# FT232_V2.net
KiCad netlist of a schematic drawn in EAGLE
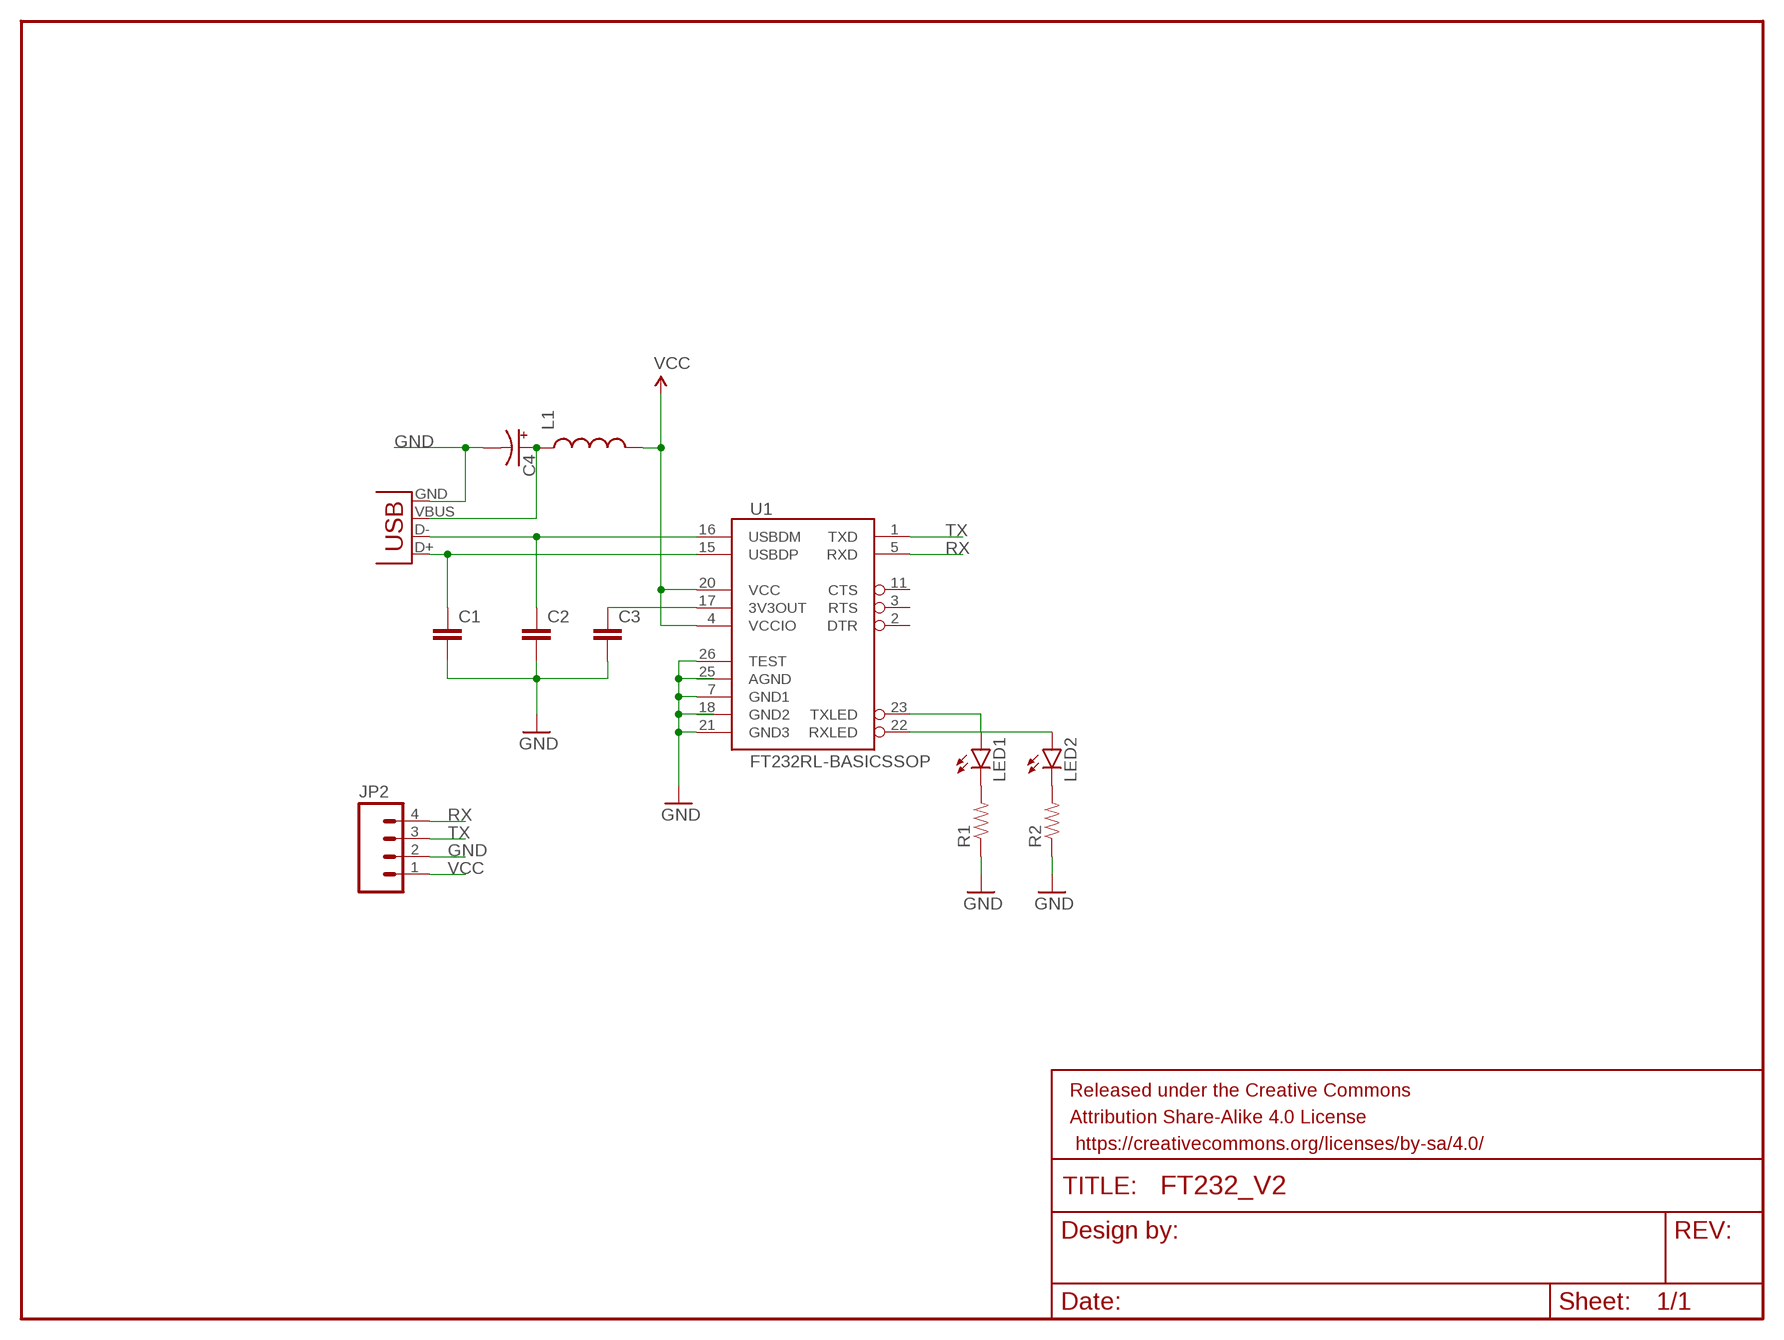
[diagram p0: schematic, sheet 1]

(export (version "E")
  (design (tool "Eeschema 10.0.6"))
  (components
    (comp (ref "C1")
      (value "CAP0603-CAP")
      (footprint "eagle-import:0603-CAP")
      (libsource (lib "eagle-import") (part "CAP0603-CAP"))
    )
    (comp (ref "C2")
      (value "CAP0603-CAP")
      (footprint "eagle-import:0603-CAP")
      (libsource (lib "eagle-import") (part "CAP0603-CAP"))
    )
    (comp (ref "C3")
      (value "CAP0603-CAP")
      (footprint "eagle-import:0603-CAP")
      (libsource (lib "eagle-import") (part "CAP0603-CAP"))
    )
    (comp (ref "C4")
      (value "CAP_POL1206")
      (footprint "eagle-import:EIA3216")
      (libsource (lib "eagle-import") (part "CAP_POL1206"))
    )
    (comp (ref "FRAME1")
      (value "FRAME-LETTER")
      (footprint "eagle-import:CREATIVE_COMMONS")
      (libsource (lib "eagle-import") (part "FRAME-LETTER"))
    )
    (comp (ref "JP1")
      (value "USB-B")
      (footprint "eagle-import:USB-B-PTH")
      (libsource (lib "eagle-import") (part "USBPTH"))
    )
    (comp (ref "JP2")
      (value "M04PTH")
      (footprint "eagle-import:1X04")
      (libsource (lib "eagle-import") (part "M04PTH"))
    )
    (comp (ref "L1")
      (value "INDUCTOR0603")
      (footprint "eagle-import:0603")
      (libsource (lib "eagle-import") (part "INDUCTOR0603"))
    )
    (comp (ref "LED1")
      (value "LED0603")
      (footprint "eagle-import:LED-0603")
      (libsource (lib "eagle-import") (part "LED0603"))
    )
    (comp (ref "LED2")
      (value "LED0603")
      (footprint "eagle-import:LED-0603")
      (libsource (lib "eagle-import") (part "LED0603"))
    )
    (comp (ref "R1")
      (value "RESISTOR0603")
      (footprint "eagle-import:0603-RES")
      (libsource (lib "eagle-import") (part "RESISTOR0603"))
    )
    (comp (ref "R2")
      (value "RESISTOR0603")
      (footprint "eagle-import:0603-RES")
      (libsource (lib "eagle-import") (part "RESISTOR0603"))
    )
    (comp (ref "U1")
      (value "FT232RL-BASICSSOP")
      (footprint "eagle-import:SSOP28DB")
      (libsource (lib "eagle-import") (part "FT232RL-BASICSSOP"))
    )
  )
  (nets
    (net (code "1") (name "/AGND") (class "Default")
      (node (ref "U1") (pin "25") (pinfunction "AGND_25") (pintype "power_in"))
    )
    (net (code "2") (name "/GND2") (class "Default")
      (node (ref "U1") (pin "18") (pinfunction "GND2_18") (pintype "power_in"))
    )
    (net (code "3") (name "/RX") (class "Default")
      (node (ref "JP2") (pin "4") (pinfunction "4_4") (pintype "passive"))
      (node (ref "U1") (pin "5") (pinfunction "RXD_5") (pintype "input"))
    )
    (net (code "4") (name "/TX") (class "Default")
      (node (ref "JP2") (pin "3") (pinfunction "3_3") (pintype "passive"))
      (node (ref "U1") (pin "1") (pinfunction "TXD_1") (pintype "output"))
    )
    (net (code "5") (name "GND") (class "Default")
      (node (ref "C1") (pin "2") (pinfunction "2_2") (pintype "passive"))
      (node (ref "C2") (pin "2") (pinfunction "2_2") (pintype "passive"))
      (node (ref "C3") (pin "2") (pinfunction "2_2") (pintype "passive"))
      (node (ref "C4") (pin "C") (pinfunction "-_C") (pintype "passive"))
      (node (ref "JP1") (pin "GND") (pinfunction "GND_GND") (pintype "bidirectional"))
      (node (ref "JP2") (pin "2") (pinfunction "2_2") (pintype "passive"))
      (node (ref "R1") (pin "1") (pinfunction "1_1") (pintype "passive"))
      (node (ref "R2") (pin "1") (pinfunction "1_1") (pintype "passive"))
      (node (ref "U1") (pin "21") (pinfunction "GND3_21") (pintype "power_in"))
      (node (ref "U1") (pin "26") (pinfunction "TEST_26") (pintype "input"))
      (node (ref "U1") (pin "7") (pinfunction "GND1_7") (pintype "power_in"))
    )
    (net (code "6") (name "Net-(C4-+)") (class "Default")
      (node (ref "C4") (pin "A") (pinfunction "+_A") (pintype "passive"))
      (node (ref "JP1") (pin "VBUS") (pinfunction "VBUS_VBUS") (pintype "bidirectional"))
      (node (ref "L1") (pin "1") (pinfunction "1_1") (pintype "passive"))
    )
    (net (code "7") (name "Net-(LED1-PadC)") (class "Default")
      (node (ref "LED1") (pin "C") (pinfunction "C_C") (pintype "passive"))
      (node (ref "R1") (pin "2") (pinfunction "2_2") (pintype "passive"))
    )
    (net (code "8") (name "Net-(LED2-PadC)") (class "Default")
      (node (ref "LED2") (pin "C") (pinfunction "C_C") (pintype "passive"))
      (node (ref "R2") (pin "2") (pinfunction "2_2") (pintype "passive"))
    )
    (net (code "9") (name "Net-(U1-3V3OUT)") (class "Default")
      (node (ref "C3") (pin "1") (pinfunction "1_1") (pintype "passive"))
      (node (ref "U1") (pin "17") (pinfunction "3V3OUT_17") (pintype "output"))
    )
    (net (code "10") (name "Net-(U1-RXLED)") (class "Default")
      (node (ref "LED2") (pin "A") (pinfunction "A_A") (pintype "passive"))
      (node (ref "U1") (pin "22") (pinfunction "RXLED_22") (pintype "bidirectional"))
    )
    (net (code "11") (name "Net-(U1-TXLED)") (class "Default")
      (node (ref "LED1") (pin "A") (pinfunction "A_A") (pintype "passive"))
      (node (ref "U1") (pin "23") (pinfunction "TXLED_23") (pintype "bidirectional"))
    )
    (net (code "12") (name "Net-(U1-USBDM)") (class "Default")
      (node (ref "C2") (pin "1") (pinfunction "1_1") (pintype "passive"))
      (node (ref "JP1") (pin "D-") (pinfunction "D-_D-") (pintype "bidirectional"))
      (node (ref "U1") (pin "16") (pinfunction "USBDM_16") (pintype "bidirectional"))
    )
    (net (code "13") (name "Net-(U1-USBDP)") (class "Default")
      (node (ref "C1") (pin "1") (pinfunction "1_1") (pintype "passive"))
      (node (ref "JP1") (pin "D+") (pinfunction "D+_D+") (pintype "bidirectional"))
      (node (ref "U1") (pin "15") (pinfunction "USBDP_15") (pintype "bidirectional"))
    )
    (net (code "14") (name "VCC") (class "Default")
      (node (ref "JP2") (pin "1") (pinfunction "1_1") (pintype "passive"))
      (node (ref "L1") (pin "2") (pinfunction "2_2") (pintype "passive"))
      (node (ref "U1") (pin "20") (pinfunction "VCC_20") (pintype "power_in"))
      (node (ref "U1") (pin "4") (pinfunction "VCCIO_4") (pintype "power_in"))
    )
    (net (code "15") (name "unconnected-(U1-CTS-Pad11)") (class "Default")
      (node (ref "U1") (pin "11") (pinfunction "CTS_11") (pintype "bidirectional"))
    )
    (net (code "16") (name "unconnected-(U1-DTR-Pad2)") (class "Default")
      (node (ref "U1") (pin "2") (pinfunction "DTR_2") (pintype "bidirectional"))
    )
    (net (code "17") (name "unconnected-(U1-RTS-Pad3)") (class "Default")
      (node (ref "U1") (pin "3") (pinfunction "RTS_3") (pintype "bidirectional"))
    )
  )
)
